# main.net
KiCad netlist of a schematic drawn in Altium Designer
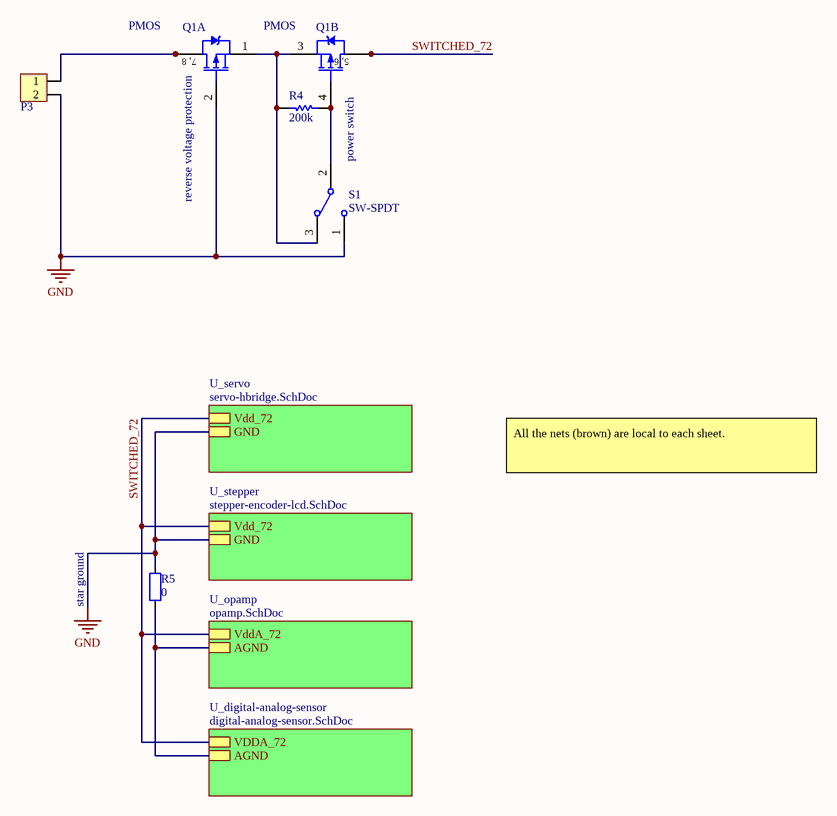
[diagram p0: main.SchDoc]

(export (version "E")
  (design (tool "Eeschema 10.0.6"))
  (components
    (comp (ref "P3")
      (value "2Way_5")
      (footprint "PCB_ConnectorCable:2Way_5")
      (description "DB")
      (libsource (lib "SCH_Connector") (part "2Way_5"))
    )
    (comp (ref "Q1")
      (value "PMOS")
      (footprint "SOIC_E200_8")
      (description "Dual PMOS")
      (fields (field (name "PUBLISHER") "Altium Limited"))
      (libsource (lib "IR Discrete MOSFET - Power") (part "IRF7316"))
    )
    (comp (ref "R4")
      (value "200k")
      (footprint "RES_0805")
      (description "Resistor")
      (fields (field (name "Comment") "Res") (field (name "PUBLISHER") "Altium Limited"))
      (libsource (lib "Miscellaneous Devices") (part "Res1"))
    )
    (comp (ref "R5")
      (value "0")
      (footprint "PCB_PassiveRes:RES_0805")
      (description "Resistor")
      (fields (field (name "Comment") "Res_0805"))
      (libsource (lib "SCH_Passive") (part "Res_0805"))
    )
    (comp (ref "S1")
      (value "SW-SPDT")
      (footprint "G3T-12AH")
      (description "SPDT Subminiature Toggle Switch, Right Angle Mounting, Vertical Actuation")
      (fields (field (name "PUBLISHER") "Altium Limited"))
      (libsource (lib "Miscellaneous Devices") (part "SW-SPDT"))
    )
  )
  (nets
    (net (code "1") (name "/AGND") (class "Default")
      (node (ref "R5") (pin "1") (pinfunction "1_1") (pintype "passive"))
    )
    (net (code "2") (name "/SWITCHED_72") (class "Default")
      (node (ref "Q1") (pin "5") (pinfunction "D_5") (pintype "passive"))
      (node (ref "Q1") (pin "6") (pinfunction "D_6") (pintype "passive"))
    )
    (net (code "3") (name "GND") (class "Default")
      (node (ref "P3") (pin "2") (pinfunction "2_2") (pintype "passive"))
      (node (ref "Q1") (pin "2") (pinfunction "G_2") (pintype "passive"))
      (node (ref "R5") (pin "2") (pinfunction "2_2") (pintype "passive"))
      (node (ref "S1") (pin "1") (pinfunction "1_1") (pintype "passive"))
    )
    (net (code "4") (name "Net-(P3-Pad1)") (class "Default")
      (node (ref "P3") (pin "1") (pinfunction "1_1") (pintype "passive"))
      (node (ref "Q1") (pin "7") (pinfunction "D_7") (pintype "passive"))
      (node (ref "Q1") (pin "8") (pinfunction "D_8") (pintype "passive"))
    )
    (net (code "5") (name "Net-(Q1A-S)") (class "Default")
      (node (ref "Q1") (pin "1") (pinfunction "S_1") (pintype "passive"))
      (node (ref "Q1") (pin "3") (pinfunction "S_3") (pintype "passive"))
      (node (ref "R4") (pin "1") (pinfunction "1_1") (pintype "passive"))
      (node (ref "S1") (pin "3") (pinfunction "3_3") (pintype "passive"))
    )
    (net (code "6") (name "Net-(Q1B-G)") (class "Default")
      (node (ref "Q1") (pin "4") (pinfunction "G_4") (pintype "passive"))
      (node (ref "R4") (pin "2") (pinfunction "2_2") (pintype "passive"))
      (node (ref "S1") (pin "2") (pinfunction "2_2") (pintype "passive"))
    )
  )
)
